# PowerPCB_90.net
KiCad netlist of a schematic drawn in EAGLE
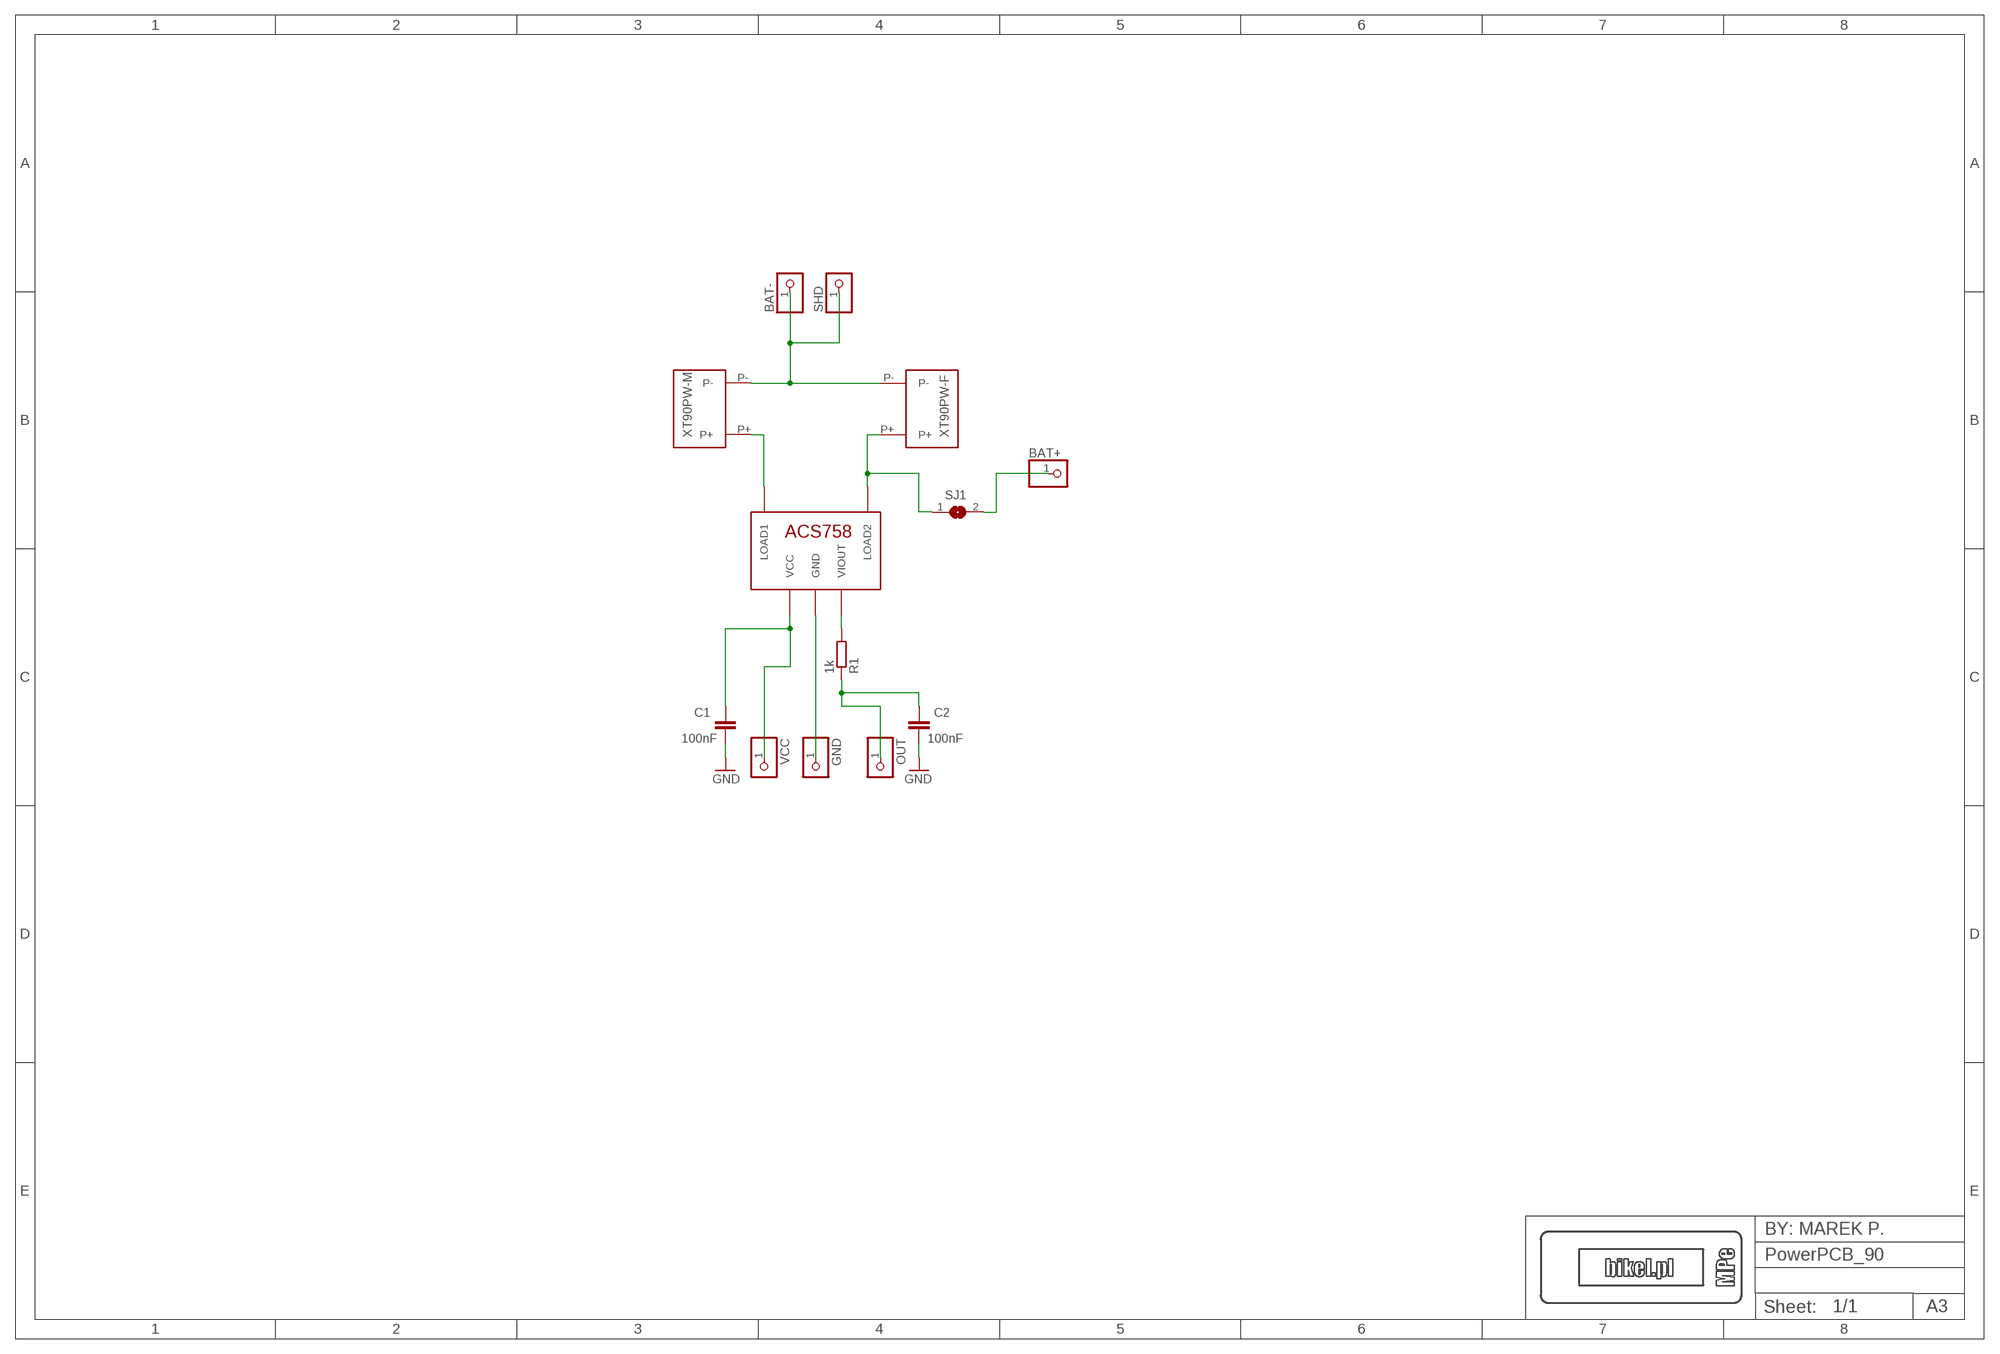
[diagram p0: schematic, sheet 1]

(export (version "E")
  (design (tool "Eeschema 10.0.6"))
  (components
    (comp (ref "ACS758_1")
      (value "ACS758")
      (footprint "eagle-import:ACS758-PFF")
      (libsource (lib "eagle-import") (part "ACS758"))
    )
    (comp (ref "BAT+")
      (value "PINHD-1X1")
      (footprint "eagle-import:1X01")
      (libsource (lib "eagle-import") (part "PINHD-1X1"))
    )
    (comp (ref "BAT-")
      (value "PINHD-1X1")
      (footprint "eagle-import:1X01")
      (libsource (lib "eagle-import") (part "PINHD-1X1"))
    )
    (comp (ref "C1")
      (value "100nF")
      (footprint "eagle-import:C0805")
      (libsource (lib "eagle-import") (part "C-EUC0805"))
    )
    (comp (ref "C2")
      (value "100nF")
      (footprint "eagle-import:C0805")
      (libsource (lib "eagle-import") (part "C-EUC0805"))
    )
    (comp (ref "GND")
      (value "PINHD-1X1")
      (footprint "eagle-import:1X01")
      (libsource (lib "eagle-import") (part "PINHD-1X1"))
    )
    (comp (ref "OUT")
      (value "PINHD-1X1")
      (footprint "eagle-import:1X01")
      (libsource (lib "eagle-import") (part "PINHD-1X1"))
    )
    (comp (ref "R1")
      (value "1k")
      (footprint "eagle-import:R0805")
      (libsource (lib "eagle-import") (part "R-EU_R0805"))
    )
    (comp (ref "SHD")
      (value "PINHD-1X1")
      (footprint "eagle-import:1X01")
      (libsource (lib "eagle-import") (part "PINHD-1X1"))
    )
    (comp (ref "SJ1") (value "SJ") (footprint "eagle-import:SJ") (libsource (lib "eagle-import") (part "SJ")))
    (comp (ref "VCC")
      (value "PINHD-1X1")
      (footprint "eagle-import:1X01")
      (libsource (lib "eagle-import") (part "PINHD-1X1"))
    )
    (comp (ref "XT90PW-F1")
      (value "XT90PW-F")
      (footprint "eagle-import:XT90PW-F")
      (libsource (lib "eagle-import") (part "XT90PW-F"))
    )
    (comp (ref "XT90PW-M1")
      (value "XT90PW-M")
      (footprint "eagle-import:XT90PW-M")
      (libsource (lib "eagle-import") (part "XT90PW-M"))
    )
  )
  (nets
    (net (code "1") (name "GND") (class "Default")
      (node (ref "ACS758_1") (pin "GND") (pinfunction "GND_GND") (pintype "bidirectional"))
      (node (ref "C1") (pin "2") (pinfunction "2_2") (pintype "passive"))
      (node (ref "C2") (pin "2") (pinfunction "2_2") (pintype "passive"))
      (node (ref "GND") (pin "1") (pinfunction "1_1") (pintype "passive"))
    )
    (net (code "2") (name "Net-(ACS758_1-PadLOAD1)") (class "Default")
      (node (ref "ACS758_1") (pin "LOAD1") (pinfunction "LOAD1_LOAD1") (pintype "bidirectional"))
      (node (ref "XT90PW-M1") (pin "P+") (pinfunction "P+_P+") (pintype "bidirectional"))
    )
    (net (code "3") (name "Net-(ACS758_1-PadLOAD2)") (class "Default")
      (node (ref "ACS758_1") (pin "LOAD2") (pinfunction "LOAD2_LOAD2") (pintype "bidirectional"))
      (node (ref "SJ1") (pin "1") (pinfunction "1_1") (pintype "passive"))
      (node (ref "XT90PW-F1") (pin "P+") (pinfunction "P+_P+") (pintype "bidirectional"))
    )
    (net (code "4") (name "Net-(ACS758_1-PadVCC)") (class "Default")
      (node (ref "ACS758_1") (pin "VCC") (pinfunction "VCC_VCC") (pintype "bidirectional"))
      (node (ref "C1") (pin "1") (pinfunction "1_1") (pintype "passive"))
      (node (ref "VCC") (pin "1") (pinfunction "1_1") (pintype "passive"))
    )
    (net (code "5") (name "Net-(ACS758_1-PadVIOUT)") (class "Default")
      (node (ref "ACS758_1") (pin "VIOUT") (pinfunction "VIOUT_VIOUT") (pintype "bidirectional"))
      (node (ref "R1") (pin "2") (pinfunction "2_2") (pintype "passive"))
    )
    (net (code "6") (name "Net-(BAT+-Pad1)") (class "Default")
      (node (ref "BAT+") (pin "1") (pinfunction "1_1") (pintype "passive"))
      (node (ref "SJ1") (pin "2") (pinfunction "2_2") (pintype "passive"))
    )
    (net (code "7") (name "Net-(BAT--Pad1)") (class "Default")
      (node (ref "BAT-") (pin "1") (pinfunction "1_1") (pintype "passive"))
      (node (ref "SHD") (pin "1") (pinfunction "1_1") (pintype "passive"))
      (node (ref "XT90PW-F1") (pin "P-") (pinfunction "P-_P-") (pintype "bidirectional"))
      (node (ref "XT90PW-M1") (pin "P-") (pinfunction "P-_P-") (pintype "bidirectional"))
    )
    (net (code "8") (name "Net-(C2-Pad1)") (class "Default")
      (node (ref "C2") (pin "1") (pinfunction "1_1") (pintype "passive"))
      (node (ref "OUT") (pin "1") (pinfunction "1_1") (pintype "passive"))
      (node (ref "R1") (pin "1") (pinfunction "1_1") (pintype "passive"))
    )
  )
)
